# ledDimmer.net
KiCad netlist of a schematic drawn in EAGLE
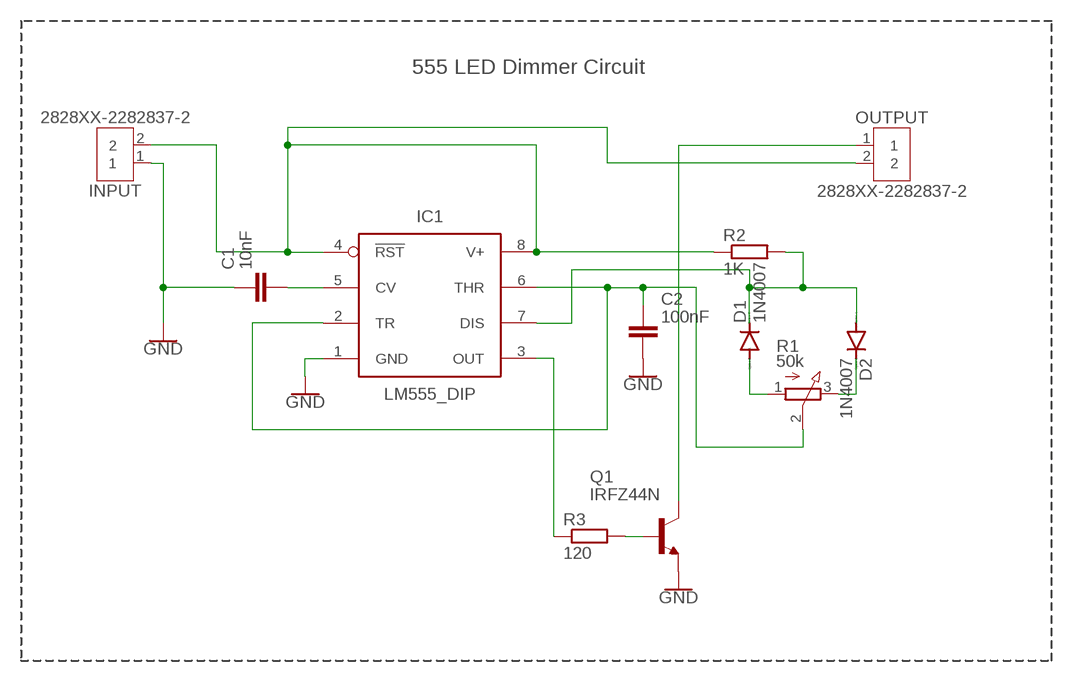
[diagram p0: schematic, sheet 1]

(export (version "E")
  (design (tool "Eeschema 10.0.6"))
  (components
    (comp (ref "C1")
      (value "10nF")
      (footprint "eagle-import:CAPC1005X60")
      (libsource (lib "eagle-import") (part "CCHIP-0402(1005-METRIC)_"))
    )
    (comp (ref "C2")
      (value "100nF")
      (footprint "eagle-import:CAPC1005X60")
      (libsource (lib "eagle-import") (part "CCHIP-0402(1005-METRIC)_"))
    )
    (comp (ref "D1")
      (value "1N4007")
      (footprint "eagle-import:DO-214AC")
      (libsource (lib "eagle-import") (part "DIODE-DO-214AC"))
    )
    (comp (ref "D2")
      (value "1N4007")
      (footprint "eagle-import:DO-214AC")
      (libsource (lib "eagle-import") (part "DIODE-DO-214AC"))
    )
    (comp (ref "IC1")
      (value "LM555_DIP")
      (footprint "eagle-import:DIP826W53P254L959H508Q8B")
      (fields (field (name "MANUFACTURER") "Texas Instruments ") (field (name "MPN") "LM555CN/NOPB "))
      (libsource (lib "eagle-import") (part "555_DIPLM"))
    )
    (comp (ref "INPUT")
      (value "2828XX-2282837-2")
      (footprint "eagle-import:TERMBLK_508-2N")
      (fields (field (name "MANUFACTURER") "TE Connectivity") (field (name "MPN") "282837-2"))
      (libsource (lib "eagle-import") (part "2828XX-2282837-2"))
    )
    (comp (ref "OUTPUT")
      (value "2828XX-2282837-2")
      (footprint "eagle-import:TERMBLK_508-2N")
      (fields (field (name "MANUFACTURER") "TE Connectivity") (field (name "MPN") "282837-2"))
      (libsource (lib "eagle-import") (part "2828XX-2282837-2"))
    )
    (comp (ref "Q1")
      (value "IRFZ44N")
      (footprint "eagle-import:TO220")
      (libsource (lib "eagle-import") (part "2N5496"))
    )
    (comp (ref "R1")
      (value "50k")
      (footprint "eagle-import:3RP_1610N")
      (libsource (lib "eagle-import") (part "3RP/1610N"))
    )
    (comp (ref "R2")
      (value "1K")
      (footprint "eagle-import:R0402")
      (libsource (lib "eagle-import") (part "R-EU_R0402"))
    )
    (comp (ref "R3")
      (value "120")
      (footprint "eagle-import:R0402")
      (libsource (lib "eagle-import") (part "R-EU_R0402"))
    )
  )
  (nets
    (net (code "1") (name "GND") (class "Default")
      (node (ref "C1") (pin "1") (pinfunction "1_1") (pintype "passive"))
      (node (ref "C2") (pin "2") (pinfunction "2_2") (pintype "passive"))
      (node (ref "IC1") (pin "1") (pinfunction "GND_1") (pintype "power_in"))
      (node (ref "INPUT") (pin "1") (pinfunction "1_1") (pintype "bidirectional"))
      (node (ref "Q1") (pin "3") (pinfunction "E_3") (pintype "passive"))
    )
    (net (code "2") (name "Net-(IC1-CV)") (class "Default")
      (node (ref "C1") (pin "2") (pinfunction "2_2") (pintype "passive"))
      (node (ref "IC1") (pin "5") (pinfunction "CV_5") (pintype "input"))
    )
    (net (code "3") (name "Net-(IC1-DIS)") (class "Default")
      (node (ref "D1") (pin "C") (pinfunction "C_C") (pintype "passive"))
      (node (ref "D2") (pin "A") (pinfunction "A_A") (pintype "passive"))
      (node (ref "IC1") (pin "7") (pinfunction "DIS_7") (pintype "input"))
      (node (ref "R2") (pin "2") (pinfunction "2_2") (pintype "passive"))
    )
    (net (code "4") (name "Net-(IC1-OUT)") (class "Default")
      (node (ref "IC1") (pin "3") (pinfunction "OUT_3") (pintype "output"))
      (node (ref "R3") (pin "1") (pinfunction "1_1") (pintype "passive"))
    )
    (net (code "5") (name "Net-(IC1-THR)") (class "Default")
      (node (ref "C2") (pin "1") (pinfunction "1_1") (pintype "passive"))
      (node (ref "IC1") (pin "2") (pinfunction "TR_2") (pintype "input"))
      (node (ref "IC1") (pin "6") (pinfunction "THR_6") (pintype "input"))
      (node (ref "R1") (pin "2") (pinfunction "S_2") (pintype "passive"))
    )
    (net (code "6") (name "Net-(IC1-V+)") (class "Default")
      (node (ref "IC1") (pin "4") (pinfunction "~{RST}_4") (pintype "input"))
      (node (ref "IC1") (pin "8") (pinfunction "V+_8") (pintype "power_in"))
      (node (ref "INPUT") (pin "2") (pinfunction "2_2") (pintype "bidirectional"))
      (node (ref "OUTPUT") (pin "2") (pinfunction "2_2") (pintype "bidirectional"))
      (node (ref "R2") (pin "1") (pinfunction "1_1") (pintype "passive"))
    )
    (net (code "7") (name "Net-(Q1-B)") (class "Default")
      (node (ref "Q1") (pin "1") (pinfunction "B_1") (pintype "passive"))
      (node (ref "R3") (pin "2") (pinfunction "2_2") (pintype "passive"))
    )
    (net (code "8") (name "Net-(Q1-C)") (class "Default")
      (node (ref "OUTPUT") (pin "1") (pinfunction "1_1") (pintype "bidirectional"))
      (node (ref "Q1") (pin "2") (pinfunction "C_2") (pintype "passive"))
    )
    (net (code "9") (name "Net-(R1-A)") (class "Default")
      (node (ref "D1") (pin "A") (pinfunction "A_A") (pintype "passive"))
      (node (ref "R1") (pin "1") (pinfunction "A_1") (pintype "passive"))
    )
    (net (code "10") (name "Net-(R1-E)") (class "Default")
      (node (ref "D2") (pin "C") (pinfunction "C_C") (pintype "passive"))
      (node (ref "R1") (pin "3") (pinfunction "E_3") (pintype "passive"))
    )
  )
)
